# BI8.net
KiCad netlist of a schematic drawn in Altium Designer
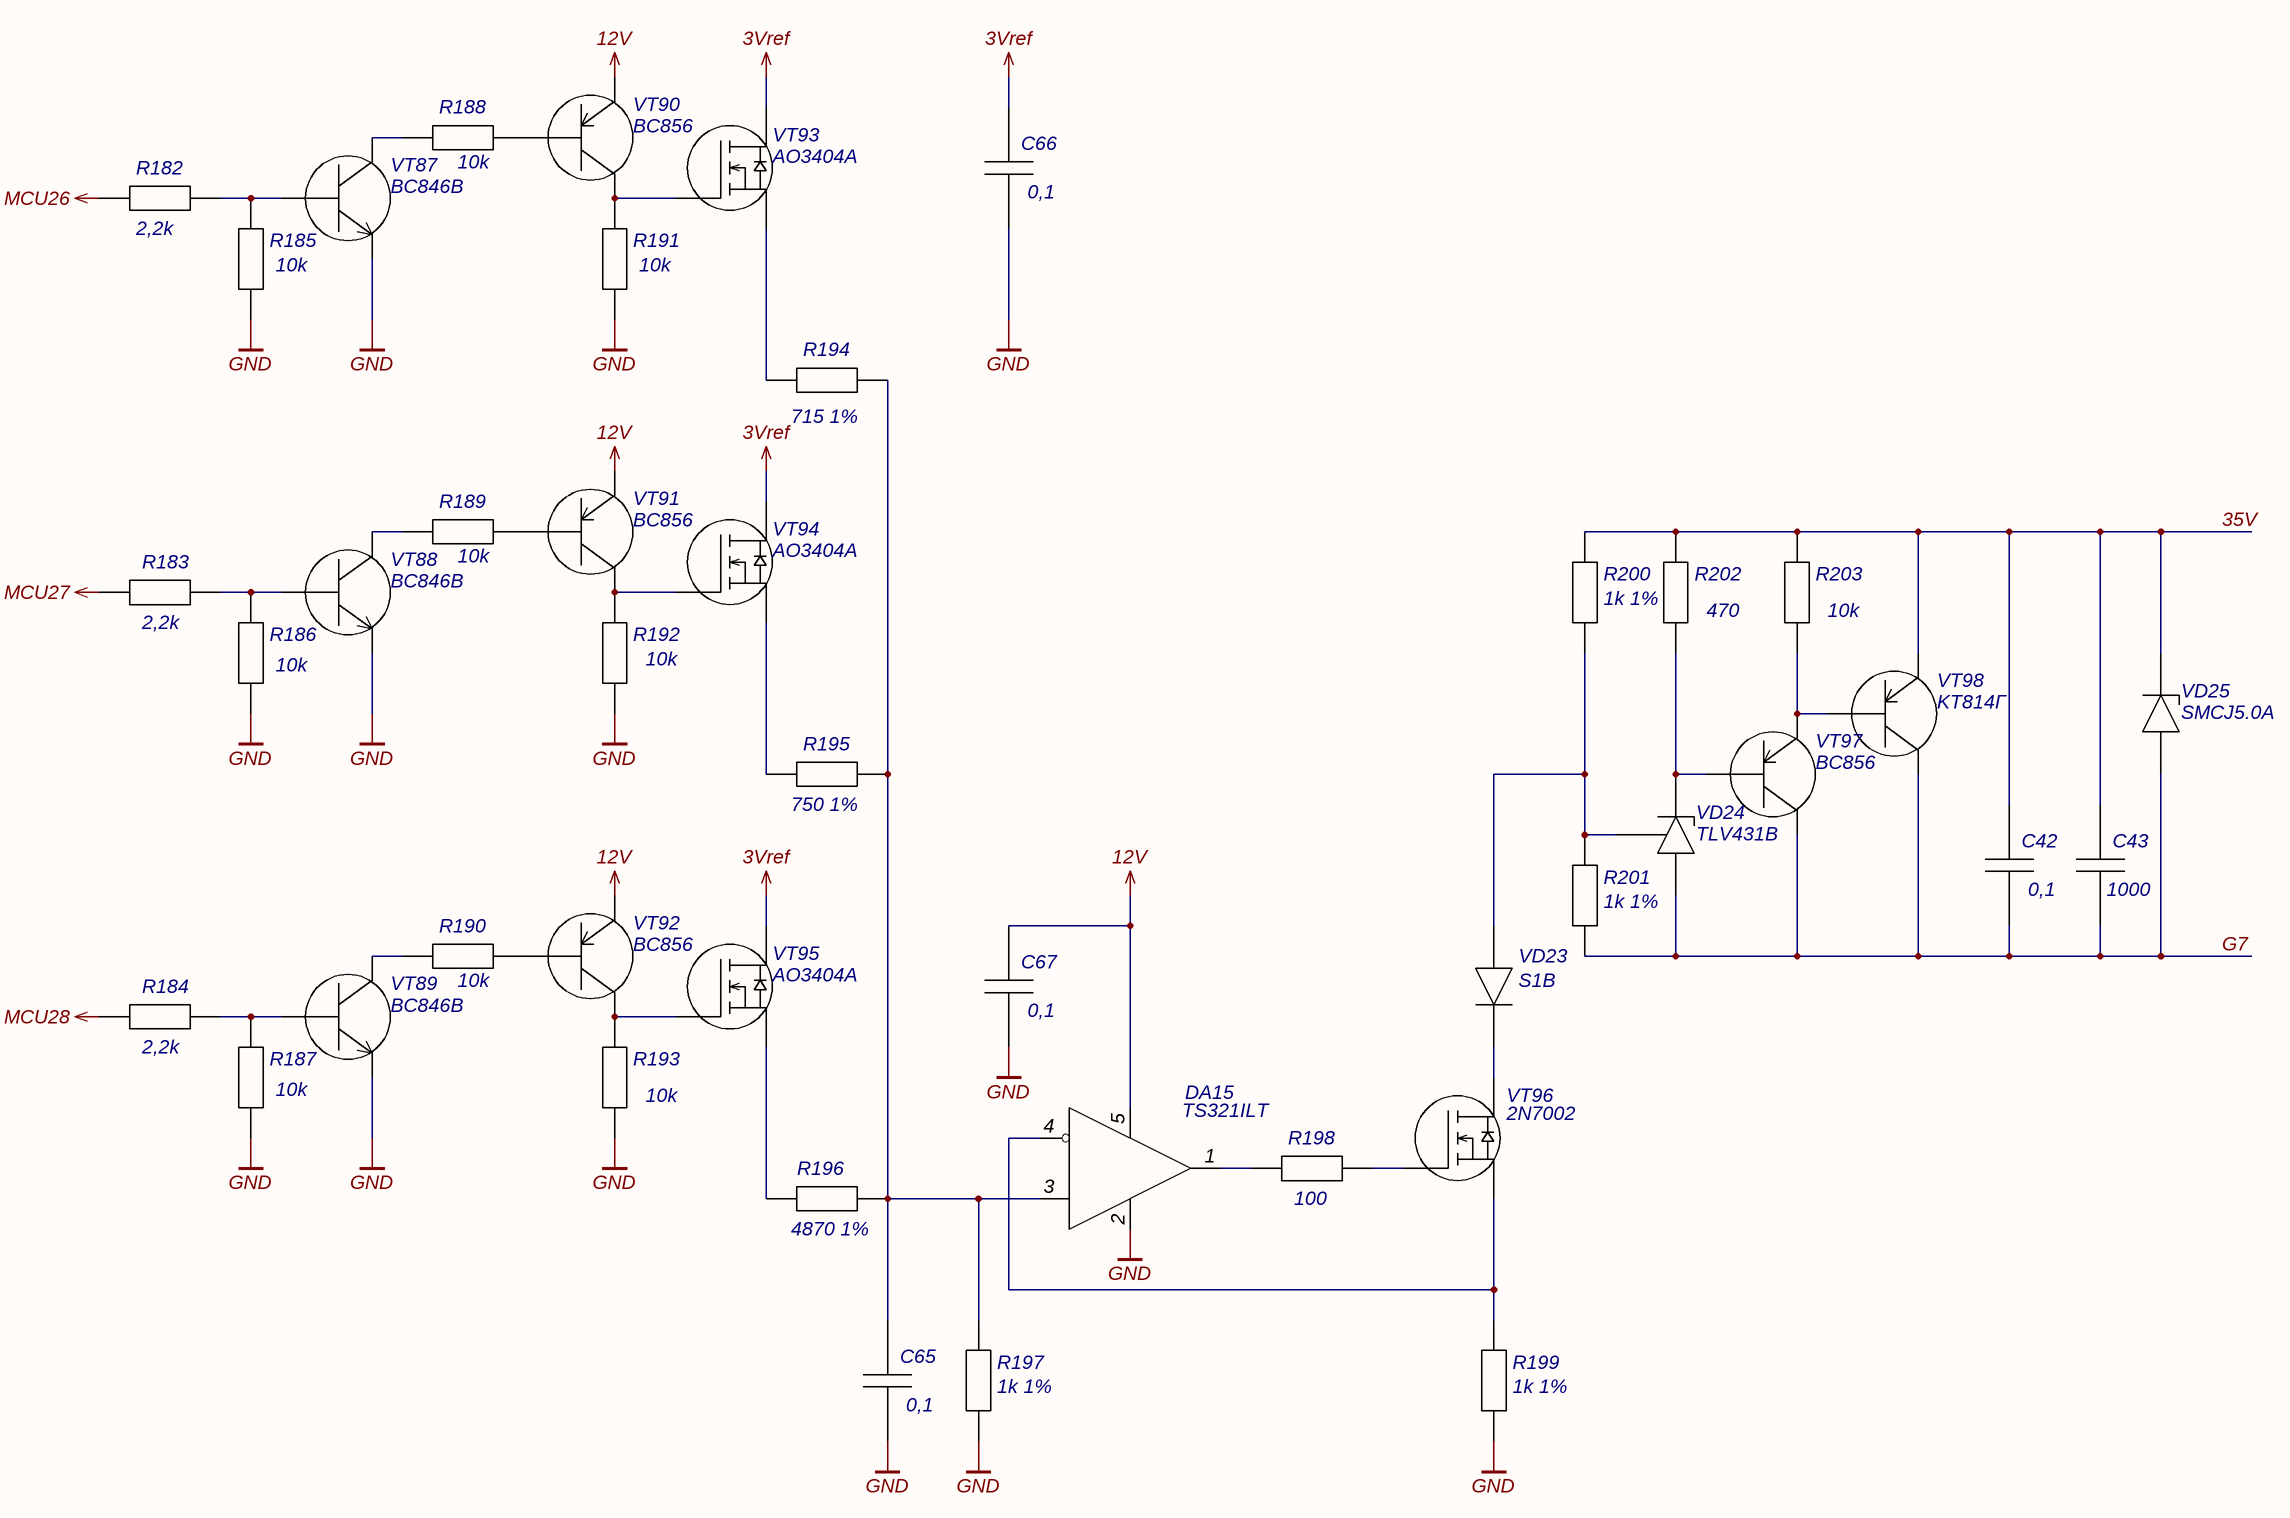
[diagram p0: BI8.SchDoc]

(export (version "E")
  (design (tool "Eeschema 10.0.6"))
  (components
    (comp (ref "C42")
      (value "0,1")
      (footprint "C0603")
      (description "Чип-конденсатор")
      (libsource (lib "Passive") (part "Chip Capasitor"))
    )
    (comp (ref "C43")
      (value "1000")
      (footprint "C0603")
      (description "Чип-конденсатор")
      (libsource (lib "Passive") (part "Chip Capasitor"))
    )
    (comp (ref "C65")
      (value "0,1")
      (footprint "C0603")
      (description "Чип-конденсатор")
      (libsource (lib "Passive") (part "Chip Capasitor"))
    )
    (comp (ref "C66")
      (value "0,1")
      (footprint "C0603")
      (description "Чип-конденсатор")
      (libsource (lib "Passive") (part "Chip Capasitor"))
    )
    (comp (ref "C67")
      (value "0,1")
      (footprint "C0603")
      (description "Чип-конденсатор")
      (libsource (lib "Passive") (part "Chip Capasitor"))
    )
    (comp (ref "DA15")
      (value "TS321ILT")
      (footprint "SOT-23-5")
      (description "1х Операционный усилитель")
      (libsource (lib "Schlib") (part "TS321ILT"))
    )
    (comp (ref "R182")
      (value "2,2k")
      (footprint "R0603")
      (description "Чип-резистор")
      (libsource (lib "Passive") (part "Chip Resistor"))
    )
    (comp (ref "R183")
      (value "2,2k")
      (footprint "R0603")
      (description "Чип-резистор")
      (libsource (lib "Passive") (part "Chip Resistor"))
    )
    (comp (ref "R184")
      (value "2,2k")
      (footprint "R0603")
      (description "Чип-резистор")
      (libsource (lib "Passive") (part "Chip Resistor"))
    )
    (comp (ref "R185")
      (value "10k")
      (footprint "R0603")
      (description "Чип-резистор")
      (libsource (lib "") (part "Chip Resistor_1"))
    )
    (comp (ref "R186")
      (value "10k")
      (footprint "R0603")
      (description "Чип-резистор")
      (libsource (lib "") (part "Chip Resistor_1"))
    )
    (comp (ref "R187")
      (value "10k")
      (footprint "R0603")
      (description "Чип-резистор")
      (libsource (lib "") (part "Chip Resistor_1"))
    )
    (comp (ref "R188")
      (value "10k")
      (footprint "R0603")
      (description "Чип-резистор")
      (libsource (lib "Passive") (part "Chip Resistor"))
    )
    (comp (ref "R189")
      (value "10k")
      (footprint "R0603")
      (description "Чип-резистор")
      (libsource (lib "Passive") (part "Chip Resistor"))
    )
    (comp (ref "R190")
      (value "10k")
      (footprint "R0603")
      (description "Чип-резистор")
      (libsource (lib "Passive") (part "Chip Resistor"))
    )
    (comp (ref "R191")
      (value "10k")
      (footprint "R0603")
      (description "Чип-резистор")
      (libsource (lib "") (part "Chip Resistor_1"))
    )
    (comp (ref "R192")
      (value "10k")
      (footprint "R0603")
      (description "Чип-резистор")
      (libsource (lib "") (part "Chip Resistor_1"))
    )
    (comp (ref "R193")
      (value "10k")
      (footprint "R0603")
      (description "Чип-резистор")
      (libsource (lib "") (part "Chip Resistor_1"))
    )
    (comp (ref "R194")
      (value "715 1%")
      (footprint "R0603")
      (description "Чип-резистор")
      (fields (field (name "PARTNUMBER") "RC0603FR-07715RL"))
      (libsource (lib "Passive") (part "Chip Resistor"))
    )
    (comp (ref "R195")
      (value "750 1%")
      (footprint "R0603")
      (description "Чип-резистор")
      (fields (field (name "PARTNUMBER") "RC0603FR-07750RL"))
      (libsource (lib "Passive") (part "Chip Resistor"))
    )
    (comp (ref "R196")
      (value "4870 1%")
      (footprint "R0603")
      (description "Чип-резистор")
      (fields (field (name "PARTNUMBER") "RC0603FR-074K87L"))
      (libsource (lib "Passive") (part "Chip Resistor"))
    )
    (comp (ref "R197")
      (value "1k 1%")
      (footprint "R0603")
      (description "Чип-резистор")
      (fields (field (name "PARTNUMBER") "CRCW06031K00FKEAC"))
      (libsource (lib "") (part "Chip Resistor_1"))
    )
    (comp (ref "R198")
      (value "100")
      (footprint "R0603")
      (description "Чип-резистор")
      (libsource (lib "Passive") (part "Chip Resistor"))
    )
    (comp (ref "R199")
      (value "1k 1%")
      (footprint "R0603")
      (description "Чип-резистор")
      (fields (field (name "PARTNUMBER") "CRCW06031K00FKEAC"))
      (libsource (lib "") (part "Chip Resistor_1"))
    )
    (comp (ref "R200")
      (value "1k 1%")
      (footprint "R0603")
      (description "Чип-резистор")
      (fields (field (name "PARTNUMBER") "CRCW06031K00FKEAC"))
      (libsource (lib "") (part "Chip Resistor_1"))
    )
    (comp (ref "R201")
      (value "1k 1%")
      (footprint "R0603")
      (description "Чип-резистор")
      (fields (field (name "PARTNUMBER") "CRCW06031K00FKEAC"))
      (libsource (lib "") (part "Chip Resistor_1"))
    )
    (comp (ref "R202")
      (value "470")
      (footprint "R0603")
      (description "Чип-резистор")
      (libsource (lib "") (part "Chip Resistor_1"))
    )
    (comp (ref "R203")
      (value "10k")
      (footprint "R0603")
      (description "Чип-резистор")
      (libsource (lib "") (part "Chip Resistor_1"))
    )
    (comp (ref "VD23")
      (value "S1B")
      (footprint "DO-214AC")
      (description "Диод выпрямительный, 100В")
      (fields (field (name "MANUFACTURER") "Diotec Semiconductor"))
      (libsource (lib "Schlib") (part "S1B"))
    )
    (comp (ref "VD24")
      (value "TLV431B")
      (footprint "SOT-23")
      (description "Стабилитрон регулируемый, 6В")
      (fields (field (name "MANUFACTURER") "Texas Instruments"))
      (libsource (lib "Schlib") (part "TLV431B"))
    )
    (comp (ref "VD25")
      (value "SMCJ5.0A")
      (footprint "DO-214AB")
      (description "Защитный диод, 5В")
      (fields (field (name "MANUFACTURER") "UTD Semiconductor Co.,Ltd"))
      (libsource (lib "Schlib") (part "SMCJ5.0A"))
    )
    (comp (ref "VT87")
      (value "BC846B")
      (footprint "SOT-23")
      (description "Транзистор биполярный NPN, 65В")
      (fields (field (name "MANUFACTURER") "Nexperia B.V."))
      (libsource (lib "Schlib") (part "BC846B"))
    )
    (comp (ref "VT88")
      (value "BC846B")
      (footprint "SOT-23")
      (description "Транзистор биполярный NPN, 65В")
      (fields (field (name "MANUFACTURER") "Nexperia B.V."))
      (libsource (lib "Schlib") (part "BC846B"))
    )
    (comp (ref "VT89")
      (value "BC846B")
      (footprint "SOT-23")
      (description "Транзистор биполярный NPN, 65В")
      (fields (field (name "MANUFACTURER") "Nexperia B.V."))
      (libsource (lib "Schlib") (part "BC846B"))
    )
    (comp (ref "VT90")
      (value "BC856")
      (footprint "SOT-23")
      (description "Транзистор биполярный PNP, 65В")
      (fields (field (name "MANUFACTURER") "Nexperia"))
      (libsource (lib "Schlib") (part "BC856"))
    )
    (comp (ref "VT91")
      (value "BC856")
      (footprint "SOT-23")
      (description "Транзистор биполярный PNP, 65В")
      (fields (field (name "MANUFACTURER") "Nexperia"))
      (libsource (lib "Schlib") (part "BC856"))
    )
    (comp (ref "VT92")
      (value "BC856")
      (footprint "SOT-23")
      (description "Транзистор биполярный PNP, 65В")
      (fields (field (name "MANUFACTURER") "Nexperia"))
      (libsource (lib "Schlib") (part "BC856"))
    )
    (comp (ref "VT93")
      (value "AO3404A")
      (footprint "SOT-23")
      (description "Транзистор MOSFET N-канал, 30В")
      (fields (field (name "MANUFACTURER") "UTD Semiconductor Co.,Ltd"))
      (libsource (lib "Schlib") (part "AO3404A"))
    )
    (comp (ref "VT94")
      (value "AO3404A")
      (footprint "SOT-23")
      (description "Транзистор MOSFET N-канал, 30В")
      (fields (field (name "MANUFACTURER") "UTD Semiconductor Co.,Ltd"))
      (libsource (lib "Schlib") (part "AO3404A"))
    )
    (comp (ref "VT95")
      (value "AO3404A")
      (footprint "SOT-23")
      (description "Транзистор MOSFET N-канал, 30В")
      (fields (field (name "MANUFACTURER") "UTD Semiconductor Co.,Ltd"))
      (libsource (lib "Schlib") (part "AO3404A"))
    )
    (comp (ref "VT96")
      (value "2N7002")
      (footprint "SOT-23")
      (description "Транзистор MOSFET N-канал, 60В")
      (fields (field (name "MANUFACTURER") "UTD Semiconductor Co."))
      (libsource (lib "Schlib") (part "2N7002"))
    )
    (comp (ref "VT97")
      (value "BC856")
      (footprint "SOT-23")
      (description "Транзистор биполярный PNP, 65В")
      (fields (field (name "MANUFACTURER") "Nexperia"))
      (libsource (lib "Schlib") (part "BC856"))
    )
    (comp (ref "VT98")
      (value "KT814Г")
      (footprint "TO-126")
      (description "Транзистор биполярный PNP, 100В")
      (fields (field (name "MANUFACTURER") "АО «ГРУППА КРЕМНИЙ ЭЛ»"))
      (libsource (lib "Schlib") (part "KT814Г"))
    )
  )
  (nets
    (net (code "1") (name "/35V") (class "Default")
      (node (ref "C42") (pin "2") (pinfunction "2_2") (pintype "passive"))
      (node (ref "C43") (pin "2") (pinfunction "2_2") (pintype "passive"))
      (node (ref "R200") (pin "2") (pinfunction "2_2") (pintype "passive"))
      (node (ref "R202") (pin "2") (pinfunction "2_2") (pintype "passive"))
      (node (ref "R203") (pin "2") (pinfunction "2_2") (pintype "passive"))
      (node (ref "VD25") (pin "2") (pinfunction "2_2") (pintype "passive"))
      (node (ref "VT98") (pin "1") (pinfunction "1_1") (pintype "passive"))
    )
    (net (code "2") (name "/G7") (class "Default")
      (node (ref "C42") (pin "1") (pinfunction "1_1") (pintype "passive"))
      (node (ref "C43") (pin "1") (pinfunction "1_1") (pintype "passive"))
      (node (ref "R201") (pin "1") (pinfunction "1_1") (pintype "passive"))
      (node (ref "VD24") (pin "1") (pinfunction "1_1") (pintype "passive"))
      (node (ref "VD25") (pin "1") (pinfunction "1_1") (pintype "passive"))
      (node (ref "VT97") (pin "2") (pinfunction "2_2") (pintype "passive"))
      (node (ref "VT98") (pin "2") (pinfunction "2_2") (pintype "passive"))
    )
    (net (code "3") (name "3Vref") (class "Default")
      (node (ref "C66") (pin "2") (pinfunction "2_2") (pintype "passive"))
      (node (ref "VT93") (pin "2") (pinfunction "D_2") (pintype "passive"))
      (node (ref "VT94") (pin "2") (pinfunction "D_2") (pintype "passive"))
      (node (ref "VT95") (pin "2") (pinfunction "D_2") (pintype "passive"))
    )
    (net (code "4") (name "12V") (class "Default")
      (node (ref "C67") (pin "2") (pinfunction "2_2") (pintype "passive"))
      (node (ref "DA15") (pin "5") (pinfunction "Vcc_5") (pintype "passive"))
      (node (ref "VT90") (pin "1") (pinfunction "1_1") (pintype "passive"))
      (node (ref "VT91") (pin "1") (pinfunction "1_1") (pintype "passive"))
      (node (ref "VT92") (pin "1") (pinfunction "1_1") (pintype "passive"))
    )
    (net (code "5") (name "GND") (class "Default")
      (node (ref "C65") (pin "1") (pinfunction "1_1") (pintype "passive"))
      (node (ref "C66") (pin "1") (pinfunction "1_1") (pintype "passive"))
      (node (ref "C67") (pin "1") (pinfunction "1_1") (pintype "passive"))
      (node (ref "DA15") (pin "2") (pinfunction "GND_2") (pintype "passive"))
      (node (ref "R185") (pin "1") (pinfunction "1_1") (pintype "passive"))
      (node (ref "R186") (pin "1") (pinfunction "1_1") (pintype "passive"))
      (node (ref "R187") (pin "1") (pinfunction "1_1") (pintype "passive"))
      (node (ref "R191") (pin "1") (pinfunction "1_1") (pintype "passive"))
      (node (ref "R192") (pin "1") (pinfunction "1_1") (pintype "passive"))
      (node (ref "R193") (pin "1") (pinfunction "1_1") (pintype "passive"))
      (node (ref "R197") (pin "1") (pinfunction "1_1") (pintype "passive"))
      (node (ref "R199") (pin "1") (pinfunction "1_1") (pintype "passive"))
      (node (ref "VT87") (pin "2") (pinfunction "E_2") (pintype "passive"))
      (node (ref "VT88") (pin "2") (pinfunction "E_2") (pintype "passive"))
      (node (ref "VT89") (pin "2") (pinfunction "E_2") (pintype "passive"))
    )
    (net (code "6") (name "MCU26") (class "Default")
      (node (ref "R182") (pin "1") (pinfunction "1_1") (pintype "passive"))
    )
    (net (code "7") (name "MCU27") (class "Default")
      (node (ref "R183") (pin "1") (pinfunction "1_1") (pintype "passive"))
    )
    (net (code "8") (name "MCU28") (class "Default")
      (node (ref "R184") (pin "1") (pinfunction "1_1") (pintype "passive"))
    )
    (net (code "9") (name "Net-(DA15-+)") (class "Default")
      (node (ref "C65") (pin "2") (pinfunction "2_2") (pintype "passive"))
      (node (ref "DA15") (pin "3") (pinfunction "+_3") (pintype "passive"))
      (node (ref "R194") (pin "2") (pinfunction "2_2") (pintype "passive"))
      (node (ref "R195") (pin "2") (pinfunction "2_2") (pintype "passive"))
      (node (ref "R196") (pin "2") (pinfunction "2_2") (pintype "passive"))
      (node (ref "R197") (pin "2") (pinfunction "2_2") (pintype "passive"))
    )
    (net (code "10") (name "Net-(DA15--)") (class "Default")
      (node (ref "DA15") (pin "4") (pinfunction "-_4") (pintype "passive"))
      (node (ref "R199") (pin "2") (pinfunction "2_2") (pintype "passive"))
      (node (ref "VT96") (pin "3") (pinfunction "S_3") (pintype "passive"))
    )
    (net (code "11") (name "Net-(DA15-OUT)") (class "Default")
      (node (ref "DA15") (pin "1") (pinfunction "OUT_1") (pintype "passive"))
      (node (ref "R198") (pin "1") (pinfunction "1_1") (pintype "passive"))
    )
    (net (code "12") (name "Net-(R188-Pad2)") (class "Default")
      (node (ref "R188") (pin "2") (pinfunction "2_2") (pintype "passive"))
      (node (ref "VT90") (pin "3") (pinfunction "3_3") (pintype "passive"))
    )
    (net (code "13") (name "Net-(R189-Pad2)") (class "Default")
      (node (ref "R189") (pin "2") (pinfunction "2_2") (pintype "passive"))
      (node (ref "VT91") (pin "3") (pinfunction "3_3") (pintype "passive"))
    )
    (net (code "14") (name "Net-(R190-Pad2)") (class "Default")
      (node (ref "R190") (pin "2") (pinfunction "2_2") (pintype "passive"))
      (node (ref "VT92") (pin "3") (pinfunction "3_3") (pintype "passive"))
    )
    (net (code "15") (name "Net-(R200-Pad1)") (class "Default")
      (node (ref "R200") (pin "1") (pinfunction "1_1") (pintype "passive"))
      (node (ref "R201") (pin "2") (pinfunction "2_2") (pintype "passive"))
      (node (ref "VD23") (pin "1") (pinfunction "1_1") (pintype "passive"))
      (node (ref "VD24") (pin "3") (pinfunction "3_3") (pintype "passive"))
    )
    (net (code "16") (name "Net-(R202-Pad1)") (class "Default")
      (node (ref "R202") (pin "1") (pinfunction "1_1") (pintype "passive"))
      (node (ref "VD24") (pin "2") (pinfunction "2_2") (pintype "passive"))
      (node (ref "VT97") (pin "3") (pinfunction "3_3") (pintype "passive"))
    )
    (net (code "17") (name "Net-(R203-Pad1)") (class "Default")
      (node (ref "R203") (pin "1") (pinfunction "1_1") (pintype "passive"))
      (node (ref "VT97") (pin "1") (pinfunction "1_1") (pintype "passive"))
      (node (ref "VT98") (pin "3") (pinfunction "3_3") (pintype "passive"))
    )
    (net (code "18") (name "Net-(VT87-B)") (class "Default")
      (node (ref "R182") (pin "2") (pinfunction "2_2") (pintype "passive"))
      (node (ref "R185") (pin "2") (pinfunction "2_2") (pintype "passive"))
      (node (ref "VT87") (pin "1") (pinfunction "B_1") (pintype "passive"))
    )
    (net (code "19") (name "Net-(VT87-C)") (class "Default")
      (node (ref "R188") (pin "1") (pinfunction "1_1") (pintype "passive"))
      (node (ref "VT87") (pin "3") (pinfunction "C_3") (pintype "passive"))
    )
    (net (code "20") (name "Net-(VT88-B)") (class "Default")
      (node (ref "R183") (pin "2") (pinfunction "2_2") (pintype "passive"))
      (node (ref "R186") (pin "2") (pinfunction "2_2") (pintype "passive"))
      (node (ref "VT88") (pin "1") (pinfunction "B_1") (pintype "passive"))
    )
    (net (code "21") (name "Net-(VT88-C)") (class "Default")
      (node (ref "R189") (pin "1") (pinfunction "1_1") (pintype "passive"))
      (node (ref "VT88") (pin "3") (pinfunction "C_3") (pintype "passive"))
    )
    (net (code "22") (name "Net-(VT89-B)") (class "Default")
      (node (ref "R184") (pin "2") (pinfunction "2_2") (pintype "passive"))
      (node (ref "R187") (pin "2") (pinfunction "2_2") (pintype "passive"))
      (node (ref "VT89") (pin "1") (pinfunction "B_1") (pintype "passive"))
    )
    (net (code "23") (name "Net-(VT89-C)") (class "Default")
      (node (ref "R190") (pin "1") (pinfunction "1_1") (pintype "passive"))
      (node (ref "VT89") (pin "3") (pinfunction "C_3") (pintype "passive"))
    )
    (net (code "24") (name "Net-(VT93-G)") (class "Default")
      (node (ref "R191") (pin "2") (pinfunction "2_2") (pintype "passive"))
      (node (ref "VT90") (pin "2") (pinfunction "2_2") (pintype "passive"))
      (node (ref "VT93") (pin "1") (pinfunction "G_1") (pintype "passive"))
    )
    (net (code "25") (name "Net-(VT93-S)") (class "Default")
      (node (ref "R194") (pin "1") (pinfunction "1_1") (pintype "passive"))
      (node (ref "VT93") (pin "3") (pinfunction "S_3") (pintype "passive"))
    )
    (net (code "26") (name "Net-(VT94-G)") (class "Default")
      (node (ref "R192") (pin "2") (pinfunction "2_2") (pintype "passive"))
      (node (ref "VT91") (pin "2") (pinfunction "2_2") (pintype "passive"))
      (node (ref "VT94") (pin "1") (pinfunction "G_1") (pintype "passive"))
    )
    (net (code "27") (name "Net-(VT94-S)") (class "Default")
      (node (ref "R195") (pin "1") (pinfunction "1_1") (pintype "passive"))
      (node (ref "VT94") (pin "3") (pinfunction "S_3") (pintype "passive"))
    )
    (net (code "28") (name "Net-(VT95-G)") (class "Default")
      (node (ref "R193") (pin "2") (pinfunction "2_2") (pintype "passive"))
      (node (ref "VT92") (pin "2") (pinfunction "2_2") (pintype "passive"))
      (node (ref "VT95") (pin "1") (pinfunction "G_1") (pintype "passive"))
    )
    (net (code "29") (name "Net-(VT95-S)") (class "Default")
      (node (ref "R196") (pin "1") (pinfunction "1_1") (pintype "passive"))
      (node (ref "VT95") (pin "3") (pinfunction "S_3") (pintype "passive"))
    )
    (net (code "30") (name "Net-(VT96-D)") (class "Default")
      (node (ref "VD23") (pin "2") (pinfunction "2_2") (pintype "passive"))
      (node (ref "VT96") (pin "2") (pinfunction "D_2") (pintype "passive"))
    )
    (net (code "31") (name "Net-(VT96-G)") (class "Default")
      (node (ref "R198") (pin "2") (pinfunction "2_2") (pintype "passive"))
      (node (ref "VT96") (pin "1") (pinfunction "G_1") (pintype "passive"))
    )
  )
)
